# RxPCB_V1-2.net
KiCad netlist of a schematic drawn in EAGLE
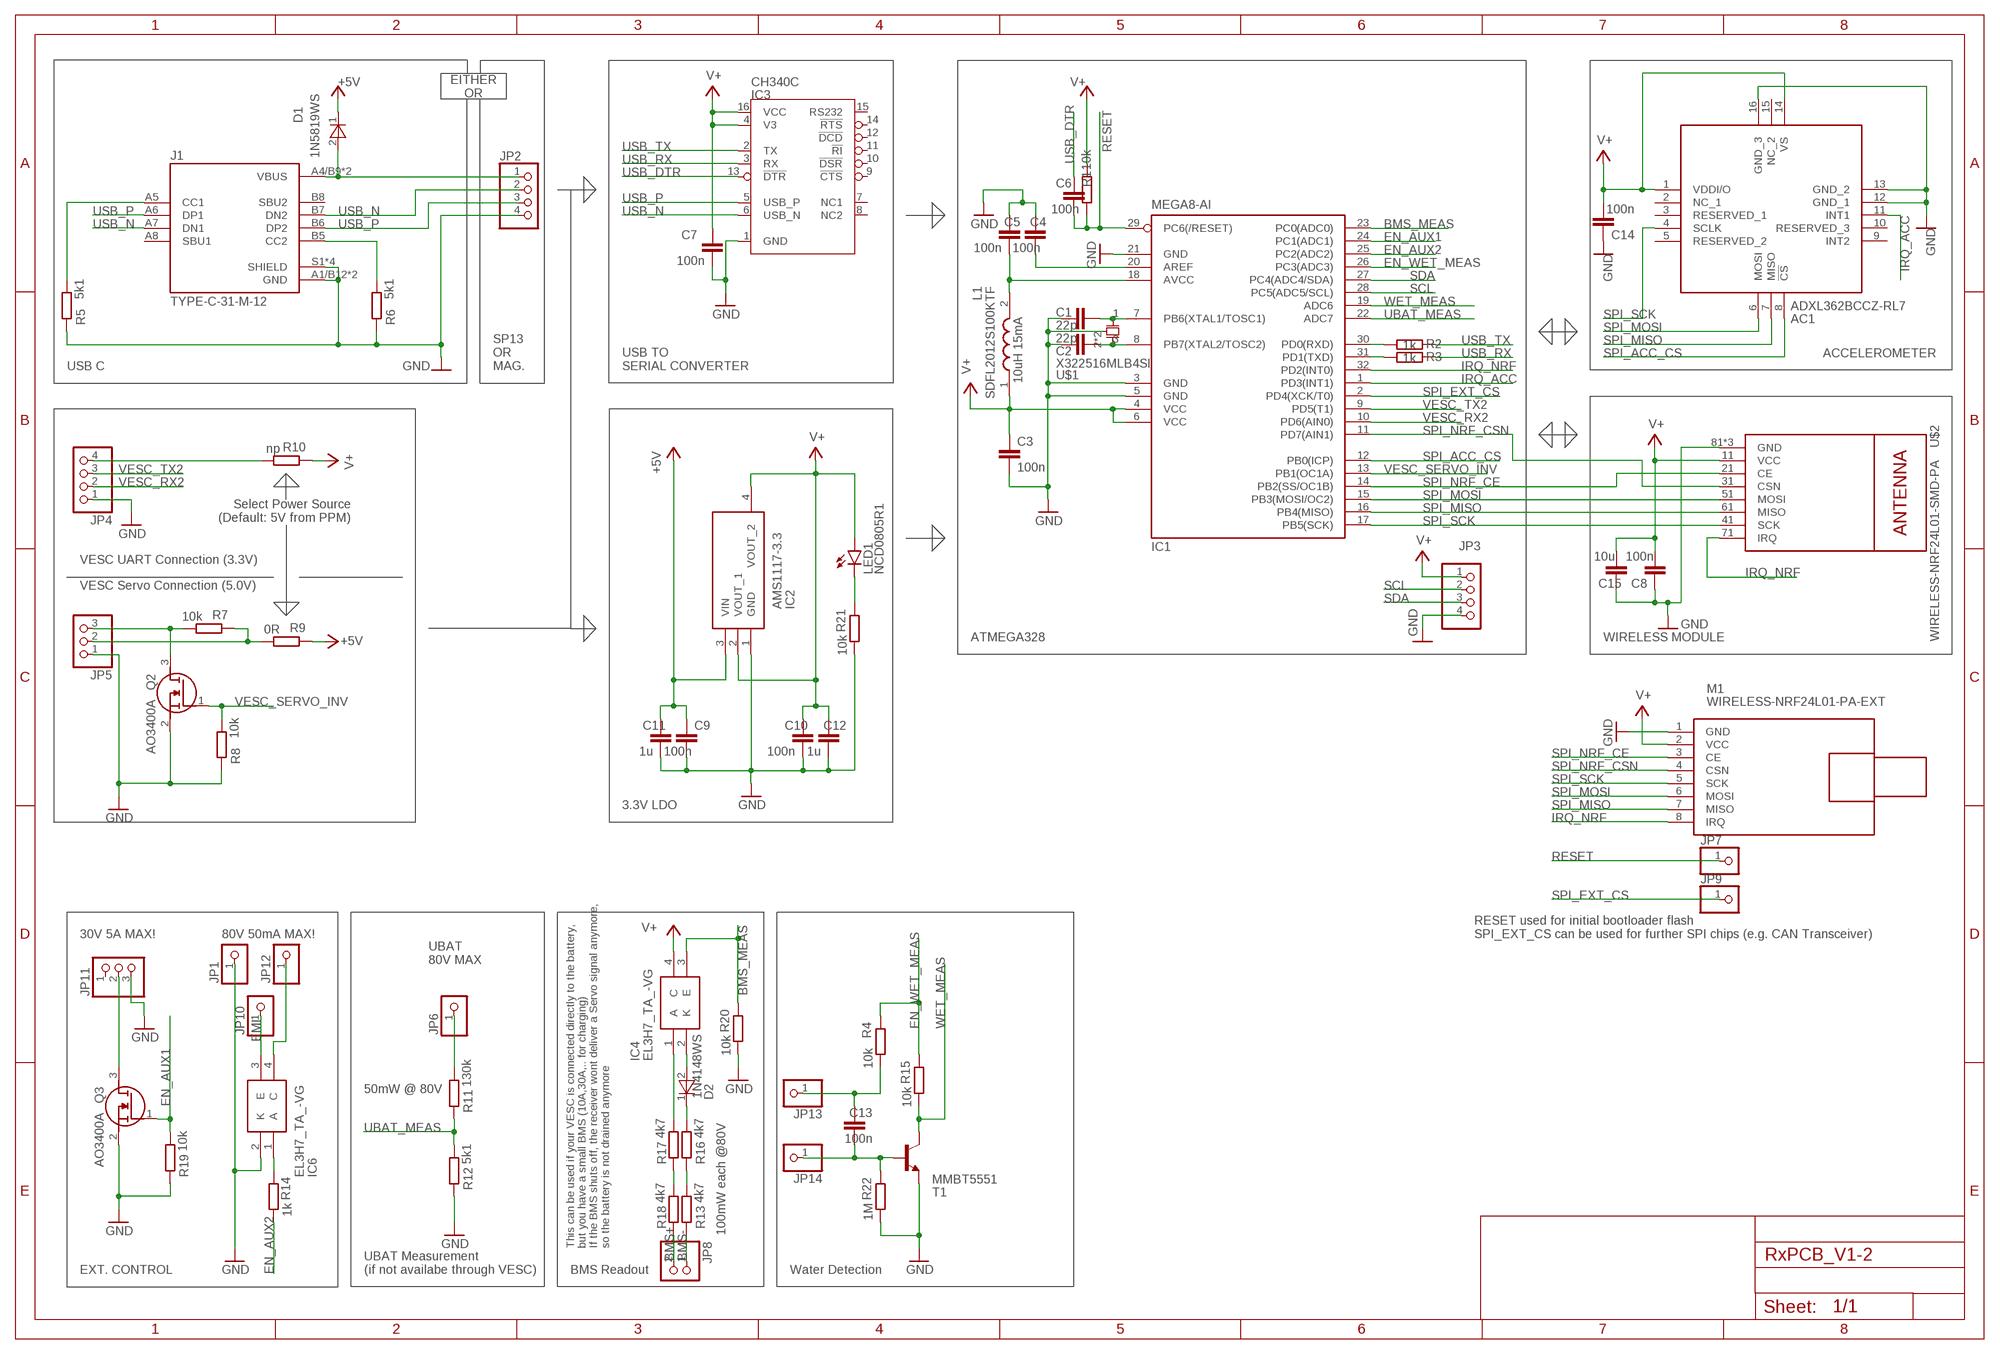
[diagram p0: schematic, sheet 1]

(export (version "E")
  (design (tool "Eeschema 10.0.6"))
  (components
    (comp (ref "AC1")
      (value "ADXL362BCCZ-RL7")
      (footprint "eagle-import:CC-16-4")
      (fields (field (name "MOUSER_PART_NUMBER") "584-ADXL362BCCZ-R7"))
      (libsource (lib "eagle-import") (part "ADXL362BCCZ-RL7"))
    )
    (comp (ref "C1")
      (value "22p")
      (footprint "eagle-import:C0603")
      (libsource (lib "eagle-import") (part "C-EUC0603"))
    )
    (comp (ref "C2")
      (value "22p")
      (footprint "eagle-import:C0603")
      (libsource (lib "eagle-import") (part "C-EUC0603"))
    )
    (comp (ref "C3")
      (value "100n")
      (footprint "eagle-import:C0603")
      (libsource (lib "eagle-import") (part "C-EUC0603"))
    )
    (comp (ref "C4")
      (value "100n")
      (footprint "eagle-import:C0603")
      (libsource (lib "eagle-import") (part "C-EUC0603"))
    )
    (comp (ref "C5")
      (value "100n")
      (footprint "eagle-import:C0603")
      (libsource (lib "eagle-import") (part "C-EUC0603"))
    )
    (comp (ref "C6")
      (value "100n")
      (footprint "eagle-import:C0603")
      (libsource (lib "eagle-import") (part "C-EUC0603"))
    )
    (comp (ref "C7")
      (value "100n")
      (footprint "eagle-import:C0603")
      (libsource (lib "eagle-import") (part "C-EUC0603"))
    )
    (comp (ref "C8")
      (value "100n")
      (footprint "eagle-import:C0603")
      (libsource (lib "eagle-import") (part "C-EUC0603"))
    )
    (comp (ref "C9")
      (value "100n")
      (footprint "eagle-import:C0603")
      (libsource (lib "eagle-import") (part "C-EUC0603"))
    )
    (comp (ref "C10")
      (value "100n")
      (footprint "eagle-import:C0603")
      (libsource (lib "eagle-import") (part "C-EUC0603"))
    )
    (comp (ref "C11")
      (value "1u")
      (footprint "eagle-import:C0603")
      (libsource (lib "eagle-import") (part "C-EUC0603"))
    )
    (comp (ref "C12")
      (value "1u")
      (footprint "eagle-import:C0603")
      (libsource (lib "eagle-import") (part "C-EUC0603"))
    )
    (comp (ref "C13")
      (value "100n")
      (footprint "eagle-import:C0603")
      (libsource (lib "eagle-import") (part "C-EUC0603"))
    )
    (comp (ref "C14")
      (value "100n")
      (footprint "eagle-import:C0603")
      (libsource (lib "eagle-import") (part "C-EUC0603"))
    )
    (comp (ref "C15")
      (value "10u")
      (footprint "eagle-import:C0603")
      (libsource (lib "eagle-import") (part "C-EUC0603"))
    )
    (comp (ref "D1")
      (value "1N5819WS")
      (footprint "eagle-import:SODFL2512X90N")
      (fields
        (field (name "ARROW_PART_NUMBER") "1N4148WS")
        (field (name "MOUSER_PART_NUMBER") "512-1N4148WS")
      )
      (libsource (lib "eagle-import") (part "1N4148WS"))
    )
    (comp (ref "D2")
      (value "1N4148WS")
      (footprint "eagle-import:SODFL2512X90N")
      (fields (field (name "MOUSER_PART_NUMBER") "512-1N4148WS"))
      (libsource (lib "eagle-import") (part "1N4148WS"))
    )
    (comp (ref "IC1")
      (value "MEGA8-AI")
      (footprint "eagle-import:TQFP32-08")
      (fields (field (name "MPN") "ATMEGA8-16AU"))
      (libsource (lib "eagle-import") (part "MEGA8-AI"))
    )
    (comp (ref "IC2")
      (value "AMS1117-3.3")
      (footprint "eagle-import:SOT229P700X180-4N")
      (libsource (lib "eagle-import") (part "AMS1117-3.3"))
    )
    (comp (ref "IC3")
      (value "CH340C")
      (footprint "eagle-import:SOIC16N")
      (libsource (lib "eagle-import") (part "CH340G"))
    )
    (comp (ref "IC4")
      (value "EL3H7_TA_-VG")
      (footprint "eagle-import:SOIC127P700X200-4N")
      (fields
        (field (name "ARROW_PART_NUMBER") "EL3H7(TA)-VG")
        (field (name "MOUSER_PART_NUMBER") "638-EL3H7TAVG")
      )
      (libsource (lib "eagle-import") (part "EL3H7_TA_-VG"))
    )
    (comp (ref "IC6")
      (value "EL3H7_TA_-VG")
      (footprint "eagle-import:SOIC127P700X200-4N")
      (fields
        (field (name "ARROW_PART_NUMBER") "EL3H7(TA)-VG")
        (field (name "MOUSER_PART_NUMBER") "638-EL3H7TAVG")
      )
      (libsource (lib "eagle-import") (part "EL3H7_TA_-VG"))
    )
    (comp (ref "J1")
      (value "TYPE-C-31-M-12")
      (footprint "eagle-import:HRO_TYPE-C-31-M-12")
      (fields (field (name "MF") "HRO Electronics Co., Ltd."))
      (libsource (lib "eagle-import") (part "TYPE-C-31-M-12"))
    )
    (comp (ref "JP1")
      (value "PINHD-1X1")
      (footprint "eagle-import:1X01")
      (libsource (lib "eagle-import") (part "PINHD-1X1"))
    )
    (comp (ref "JP2")
      (value "PINHD-1X4")
      (footprint "eagle-import:1X04")
      (libsource (lib "eagle-import") (part "PINHD-1X4"))
    )
    (comp (ref "JP3")
      (value "PINHD-1X4")
      (footprint "eagle-import:1X04")
      (libsource (lib "eagle-import") (part "PINHD-1X4"))
    )
    (comp (ref "JP4")
      (value "PINHD-1X4")
      (footprint "eagle-import:1X04")
      (libsource (lib "eagle-import") (part "PINHD-1X4"))
    )
    (comp (ref "JP5")
      (value "PINHD-1X3")
      (footprint "eagle-import:1X03")
      (libsource (lib "eagle-import") (part "PINHD-1X3"))
    )
    (comp (ref "JP6")
      (value "PINHD-1X1")
      (footprint "eagle-import:1X01")
      (libsource (lib "eagle-import") (part "PINHD-1X1"))
    )
    (comp (ref "JP7")
      (value "PINHD-1X1")
      (footprint "eagle-import:1X01")
      (libsource (lib "eagle-import") (part "PINHD-1X1"))
    )
    (comp (ref "JP8")
      (value "PINHD-1X2")
      (footprint "eagle-import:1X02")
      (libsource (lib "eagle-import") (part "PINHD-1X2"))
    )
    (comp (ref "JP9")
      (value "PINHD-1X1")
      (footprint "eagle-import:1X01")
      (libsource (lib "eagle-import") (part "PINHD-1X1"))
    )
    (comp (ref "JP10")
      (value "PINHD-1X1")
      (footprint "eagle-import:1X01")
      (libsource (lib "eagle-import") (part "PINHD-1X1"))
    )
    (comp (ref "JP11")
      (value "PINHD-1X3")
      (footprint "eagle-import:1X03")
      (libsource (lib "eagle-import") (part "PINHD-1X3"))
    )
    (comp (ref "JP12")
      (value "PINHD-1X1")
      (footprint "eagle-import:1X01")
      (libsource (lib "eagle-import") (part "PINHD-1X1"))
    )
    (comp (ref "JP13")
      (value "PINHD-1X1")
      (footprint "eagle-import:1X01")
      (libsource (lib "eagle-import") (part "PINHD-1X1"))
    )
    (comp (ref "JP14")
      (value "PINHD-1X1")
      (footprint "eagle-import:1X01")
      (libsource (lib "eagle-import") (part "PINHD-1X1"))
    )
    (comp (ref "L1")
      (value "SDFL2012S100KTF")
      (footprint "eagle-import:INDC2112X105N")
      (fields (field (name "MANUFACTURER_PART_NUMBER") "SDFL2012Q2R7KTF"))
      (libsource (lib "eagle-import") (part "SDFL2012Q2R7KTF"))
    )
    (comp (ref "LED1")
      (value "NCD0805R1")
      (footprint "eagle-import:CHIP-LED0805")
      (libsource (lib "eagle-import") (part "LEDCHIP-LED0805"))
    )
    (comp (ref "M1")
      (value "WIRELESS-NRF24L01-PA-EXT")
      (footprint "eagle-import:WIRELESS-NRF24L01-PA-EXT")
      (libsource (lib "eagle-import") (part "WIRELESS-NRF24L01-PA-EXT"))
    )
    (comp (ref "Q2")
      (value "AO3400A")
      (footprint "eagle-import:SOT95P280X125-3N")
      (libsource (lib "eagle-import") (part "AO3400A"))
    )
    (comp (ref "Q3")
      (value "AO3400A")
      (footprint "eagle-import:SOT95P280X125-3N")
      (libsource (lib "eagle-import") (part "AO3400A"))
    )
    (comp (ref "R1")
      (value "10k")
      (footprint "eagle-import:R0603")
      (libsource (lib "eagle-import") (part "R-EU_R0603"))
    )
    (comp (ref "R2")
      (value "1k")
      (footprint "eagle-import:R0603")
      (libsource (lib "eagle-import") (part "R-EU_R0603"))
    )
    (comp (ref "R3")
      (value "1k")
      (footprint "eagle-import:R0603")
      (libsource (lib "eagle-import") (part "R-EU_R0603"))
    )
    (comp (ref "R4")
      (value "10k")
      (footprint "eagle-import:R0603")
      (libsource (lib "eagle-import") (part "R-EU_R0603"))
    )
    (comp (ref "R5")
      (value "5k1")
      (footprint "eagle-import:R0603")
      (libsource (lib "eagle-import") (part "R-EU_R0603"))
    )
    (comp (ref "R6")
      (value "5k1")
      (footprint "eagle-import:R0603")
      (libsource (lib "eagle-import") (part "R-EU_R0603"))
    )
    (comp (ref "R7")
      (value "10k")
      (footprint "eagle-import:R0603")
      (libsource (lib "eagle-import") (part "R-EU_R0603"))
    )
    (comp (ref "R8")
      (value "10k")
      (footprint "eagle-import:R0603")
      (libsource (lib "eagle-import") (part "R-EU_R0603"))
    )
    (comp (ref "R9")
      (value "0R")
      (footprint "eagle-import:R0603")
      (libsource (lib "eagle-import") (part "R-EU_R0603"))
    )
    (comp (ref "R10")
      (value "np")
      (footprint "eagle-import:R0603")
      (libsource (lib "eagle-import") (part "R-EU_R0603"))
    )
    (comp (ref "R11")
      (value "130k")
      (footprint "eagle-import:R0603")
      (libsource (lib "eagle-import") (part "R-EU_R0603"))
    )
    (comp (ref "R12")
      (value "5k1")
      (footprint "eagle-import:R0603")
      (libsource (lib "eagle-import") (part "R-EU_R0603"))
    )
    (comp (ref "R13")
      (value "4k7")
      (footprint "eagle-import:R0603")
      (libsource (lib "eagle-import") (part "R-EU_R0603"))
    )
    (comp (ref "R14")
      (value "1k")
      (footprint "eagle-import:R0603")
      (libsource (lib "eagle-import") (part "R-EU_R0603"))
    )
    (comp (ref "R15")
      (value "10k")
      (footprint "eagle-import:R0603")
      (libsource (lib "eagle-import") (part "R-EU_R0603"))
    )
    (comp (ref "R16")
      (value "4k7")
      (footprint "eagle-import:R0603")
      (libsource (lib "eagle-import") (part "R-EU_R0603"))
    )
    (comp (ref "R17")
      (value "4k7")
      (footprint "eagle-import:R0603")
      (libsource (lib "eagle-import") (part "R-EU_R0603"))
    )
    (comp (ref "R18")
      (value "4k7")
      (footprint "eagle-import:R0603")
      (libsource (lib "eagle-import") (part "R-EU_R0603"))
    )
    (comp (ref "R19")
      (value "10k")
      (footprint "eagle-import:R0603")
      (libsource (lib "eagle-import") (part "R-EU_R0603"))
    )
    (comp (ref "R20")
      (value "10k")
      (footprint "eagle-import:R0603")
      (libsource (lib "eagle-import") (part "R-EU_R0603"))
    )
    (comp (ref "R21")
      (value "10k")
      (footprint "eagle-import:R0603")
      (libsource (lib "eagle-import") (part "R-EU_R0603"))
    )
    (comp (ref "R22")
      (value "1M")
      (footprint "eagle-import:R0603")
      (libsource (lib "eagle-import") (part "R-EU_R0603"))
    )
    (comp (ref "T1")
      (value "MMBT5551")
      (footprint "eagle-import:SOT23-BEC")
      (libsource (lib "eagle-import") (part "-NPN-SOT23-BECBC847B"))
    )
    (comp (ref "U$1")
      (value "X322516MLB4SI")
      (footprint "eagle-import:X322516MLB4SI")
      (libsource (lib "eagle-import") (part "X322516_BETTER"))
    )
    (comp (ref "U$2")
      (value "WIRELESS-NRF24L01-SMD-PA")
      (footprint "eagle-import:WIRELESS-NRF24L01_SMD_PA")
      (libsource (lib "eagle-import") (part "WIRELESS-NRF24L01-SMD-PA"))
    )
  )
  (nets
    (net (code "1") (name "+5V") (class "Default")
      (node (ref "C11") (pin "1") (pinfunction "1_1") (pintype "passive"))
      (node (ref "C9") (pin "1") (pinfunction "1_1") (pintype "passive"))
      (node (ref "D1") (pin "1") (pinfunction "K_1") (pintype "bidirectional"))
      (node (ref "IC2") (pin "3") (pinfunction "VIN_3") (pintype "bidirectional"))
      (node (ref "R9") (pin "1") (pinfunction "1_1") (pintype "passive"))
    )
    (net (code "2") (name "/BMS+") (class "Default")
      (node (ref "JP8") (pin "2") (pinfunction "2_2") (pintype "passive"))
      (node (ref "R18") (pin "1") (pinfunction "1_1") (pintype "passive"))
    )
    (net (code "3") (name "/BMS-") (class "Default")
      (node (ref "JP8") (pin "1") (pinfunction "1_1") (pintype "passive"))
      (node (ref "R13") (pin "1") (pinfunction "1_1") (pintype "passive"))
    )
    (net (code "4") (name "/BMS_MEAS") (class "Default")
      (node (ref "IC1") (pin "23") (pinfunction "PC0(ADC0)_23") (pintype "bidirectional"))
      (node (ref "IC4") (pin "3") (pinfunction "E_3") (pintype "bidirectional"))
      (node (ref "R20") (pin "1") (pinfunction "1_1") (pintype "passive"))
    )
    (net (code "5") (name "/EMI") (class "Default")
      (node (ref "IC6") (pin "3") (pinfunction "E_3") (pintype "bidirectional"))
      (node (ref "JP10") (pin "1") (pinfunction "1_1") (pintype "passive"))
    )
    (net (code "6") (name "/EN_AUX1") (class "Default")
      (node (ref "IC1") (pin "24") (pinfunction "PC1(ADC1)_24") (pintype "bidirectional"))
      (node (ref "Q3") (pin "1") (pinfunction "G_1") (pintype "bidirectional"))
      (node (ref "R19") (pin "2") (pinfunction "2_2") (pintype "passive"))
    )
    (net (code "7") (name "/EN_AUX2") (class "Default")
      (node (ref "IC1") (pin "25") (pinfunction "PC2(ADC2)_25") (pintype "bidirectional"))
      (node (ref "R14") (pin "2") (pinfunction "2_2") (pintype "passive"))
    )
    (net (code "8") (name "/EN_WET_MEAS") (class "Default")
      (node (ref "IC1") (pin "26") (pinfunction "PC3(ADC3)_26") (pintype "bidirectional"))
      (node (ref "R15") (pin "1") (pinfunction "1_1") (pintype "passive"))
      (node (ref "R4") (pin "1") (pinfunction "1_1") (pintype "passive"))
    )
    (net (code "9") (name "/IRQ_ACC") (class "Default")
      (node (ref "AC1") (pin "11") (pinfunction "INT1_11") (pintype "input"))
      (node (ref "IC1") (pin "1") (pinfunction "PD3(INT1)_1") (pintype "bidirectional"))
    )
    (net (code "10") (name "/IRQ_NRF") (class "Default")
      (node (ref "IC1") (pin "32") (pinfunction "PD2(INT0)_32") (pintype "bidirectional"))
      (node (ref "M1") (pin "8") (pinfunction "IRQ_8") (pintype "bidirectional"))
      (node (ref "U$2") (pin "71") (pinfunction "IRQ_71") (pintype "bidirectional"))
    )
    (net (code "11") (name "/RESET") (class "Default")
      (node (ref "C6") (pin "2") (pinfunction "2_2") (pintype "passive"))
      (node (ref "IC1") (pin "29") (pinfunction "PC6(/RESET)_29") (pintype "bidirectional"))
      (node (ref "JP7") (pin "1") (pinfunction "1_1") (pintype "passive"))
      (node (ref "R1") (pin "1") (pinfunction "1_1") (pintype "passive"))
    )
    (net (code "12") (name "/SCL") (class "Default")
      (node (ref "IC1") (pin "28") (pinfunction "PC5(ADC5/SCL)_28") (pintype "bidirectional"))
      (node (ref "JP3") (pin "2") (pinfunction "2_2") (pintype "passive"))
    )
    (net (code "13") (name "/SDA") (class "Default")
      (node (ref "IC1") (pin "27") (pinfunction "PC4(ADC4/SDA)_27") (pintype "bidirectional"))
      (node (ref "JP3") (pin "3") (pinfunction "3_3") (pintype "passive"))
    )
    (net (code "14") (name "/SPI_ACC_CS") (class "Default")
      (node (ref "AC1") (pin "8") (pinfunction "~{CS}_8") (pintype "input"))
      (node (ref "IC1") (pin "12") (pinfunction "PB0(ICP)_12") (pintype "bidirectional"))
    )
    (net (code "15") (name "/SPI_EXT_CS") (class "Default")
      (node (ref "IC1") (pin "2") (pinfunction "PD4(XCK/T0)_2") (pintype "bidirectional"))
      (node (ref "JP9") (pin "1") (pinfunction "1_1") (pintype "passive"))
    )
    (net (code "16") (name "/SPI_MISO") (class "Default")
      (node (ref "AC1") (pin "7") (pinfunction "MISO_7") (pintype "bidirectional"))
      (node (ref "IC1") (pin "16") (pinfunction "PB4(MISO)_16") (pintype "bidirectional"))
      (node (ref "M1") (pin "7") (pinfunction "MISO_7") (pintype "bidirectional"))
      (node (ref "U$2") (pin "61") (pinfunction "MISO_61") (pintype "bidirectional"))
    )
    (net (code "17") (name "/SPI_MOSI") (class "Default")
      (node (ref "AC1") (pin "6") (pinfunction "MOSI_6") (pintype "bidirectional"))
      (node (ref "IC1") (pin "15") (pinfunction "PB3(MOSI/OC2)_15") (pintype "bidirectional"))
      (node (ref "M1") (pin "6") (pinfunction "MOSI_6") (pintype "bidirectional"))
      (node (ref "U$2") (pin "51") (pinfunction "MOSI_51") (pintype "bidirectional"))
    )
    (net (code "18") (name "/SPI_NRF_CE") (class "Default")
      (node (ref "IC1") (pin "14") (pinfunction "PB2(SS/OC1B)_14") (pintype "bidirectional"))
      (node (ref "M1") (pin "3") (pinfunction "CE_3") (pintype "bidirectional"))
      (node (ref "U$2") (pin "21") (pinfunction "CE_21") (pintype "bidirectional"))
    )
    (net (code "19") (name "/SPI_NRF_CSN") (class "Default")
      (node (ref "IC1") (pin "11") (pinfunction "PD7(AIN1)_11") (pintype "bidirectional"))
      (node (ref "M1") (pin "4") (pinfunction "CSN_4") (pintype "bidirectional"))
      (node (ref "U$2") (pin "31") (pinfunction "CSN_31") (pintype "bidirectional"))
    )
    (net (code "20") (name "/SPI_SCK") (class "Default")
      (node (ref "AC1") (pin "4") (pinfunction "SCLK_4") (pintype "input"))
      (node (ref "IC1") (pin "17") (pinfunction "PB5(SCK)_17") (pintype "bidirectional"))
      (node (ref "M1") (pin "5") (pinfunction "SCK_5") (pintype "bidirectional"))
      (node (ref "U$2") (pin "41") (pinfunction "SCK_41") (pintype "bidirectional"))
    )
    (net (code "21") (name "/UBAT_MEAS") (class "Default")
      (node (ref "IC1") (pin "22") (pinfunction "ADC7_22") (pintype "bidirectional"))
      (node (ref "R11") (pin "1") (pinfunction "1_1") (pintype "passive"))
      (node (ref "R12") (pin "2") (pinfunction "2_2") (pintype "passive"))
    )
    (net (code "22") (name "/USB_DTR") (class "Default")
      (node (ref "C6") (pin "1") (pinfunction "1_1") (pintype "passive"))
      (node (ref "IC3") (pin "13") (pinfunction "~{DTR}_13") (pintype "output"))
    )
    (net (code "23") (name "/USB_N") (class "Default")
      (node (ref "IC3") (pin "6") (pinfunction "USB_N_6") (pintype "bidirectional"))
      (node (ref "J1") (pin "A7") (pinfunction "DN1_A7") (pintype "bidirectional"))
      (node (ref "J1") (pin "B7") (pinfunction "DN2_B7") (pintype "bidirectional"))
      (node (ref "JP2") (pin "2") (pinfunction "2_2") (pintype "passive"))
    )
    (net (code "24") (name "/USB_P") (class "Default")
      (node (ref "IC3") (pin "5") (pinfunction "USB_P_5") (pintype "bidirectional"))
      (node (ref "J1") (pin "A6") (pinfunction "DP1_A6") (pintype "bidirectional"))
      (node (ref "J1") (pin "B6") (pinfunction "DP2_B6") (pintype "bidirectional"))
      (node (ref "JP2") (pin "3") (pinfunction "3_3") (pintype "passive"))
    )
    (net (code "25") (name "/USB_RX") (class "Default")
      (node (ref "IC3") (pin "3") (pinfunction "RX_3") (pintype "input"))
      (node (ref "R3") (pin "1") (pinfunction "1_1") (pintype "passive"))
    )
    (net (code "26") (name "/USB_TX") (class "Default")
      (node (ref "IC3") (pin "2") (pinfunction "TX_2") (pintype "output"))
      (node (ref "R2") (pin "1") (pinfunction "1_1") (pintype "passive"))
    )
    (net (code "27") (name "/VESC_RX2") (class "Default")
      (node (ref "IC1") (pin "10") (pinfunction "PD6(AIN0)_10") (pintype "bidirectional"))
      (node (ref "JP4") (pin "2") (pinfunction "2_2") (pintype "passive"))
    )
    (net (code "28") (name "/VESC_SERVO_INV") (class "Default")
      (node (ref "IC1") (pin "13") (pinfunction "PB1(OC1A)_13") (pintype "bidirectional"))
      (node (ref "Q2") (pin "1") (pinfunction "G_1") (pintype "bidirectional"))
      (node (ref "R8") (pin "2") (pinfunction "2_2") (pintype "passive"))
    )
    (net (code "29") (name "/VESC_TX2") (class "Default")
      (node (ref "IC1") (pin "9") (pinfunction "PD5(T1)_9") (pintype "bidirectional"))
      (node (ref "JP4") (pin "3") (pinfunction "3_3") (pintype "passive"))
    )
    (net (code "30") (name "/WET_MEAS") (class "Default")
      (node (ref "IC1") (pin "19") (pinfunction "ADC6_19") (pintype "bidirectional"))
      (node (ref "R15") (pin "2") (pinfunction "2_2") (pintype "passive"))
      (node (ref "T1") (pin "C") (pinfunction "C_C") (pintype "passive"))
    )
    (net (code "31") (name "GND") (class "Default")
      (node (ref "AC1") (pin "12") (pinfunction "GND_1_12") (pintype "power_in"))
      (node (ref "AC1") (pin "13") (pinfunction "GND_2_13") (pintype "power_in"))
      (node (ref "AC1") (pin "16") (pinfunction "GND_3_16") (pintype "power_in"))
      (node (ref "C1") (pin "2") (pinfunction "2_2") (pintype "passive"))
      (node (ref "C10") (pin "2") (pinfunction "2_2") (pintype "passive"))
      (node (ref "C11") (pin "2") (pinfunction "2_2") (pintype "passive"))
      (node (ref "C12") (pin "2") (pinfunction "2_2") (pintype "passive"))
      (node (ref "C14") (pin "1") (pinfunction "1_1") (pintype "passive"))
      (node (ref "C15") (pin "2") (pinfunction "2_2") (pintype "passive"))
      (node (ref "C2") (pin "2") (pinfunction "2_2") (pintype "passive"))
      (node (ref "C3") (pin "2") (pinfunction "2_2") (pintype "passive"))
      (node (ref "C4") (pin "1") (pinfunction "1_1") (pintype "passive"))
      (node (ref "C5") (pin "1") (pinfunction "1_1") (pintype "passive"))
      (node (ref "C7") (pin "2") (pinfunction "2_2") (pintype "passive"))
      (node (ref "C8") (pin "1") (pinfunction "1_1") (pintype "passive"))
      (node (ref "C9") (pin "2") (pinfunction "2_2") (pintype "passive"))
      (node (ref "IC1") (pin "21") (pinfunction "GND_21") (pintype "power_in"))
      (node (ref "IC1") (pin "3") (pinfunction "GND_3") (pintype "power_in"))
      (node (ref "IC1") (pin "5") (pinfunction "GND_5") (pintype "power_in"))
      (node (ref "IC2") (pin "1") (pinfunction "GND_1") (pintype "bidirectional"))
      (node (ref "IC3") (pin "1") (pinfunction "GND_1") (pintype "input"))
      (node (ref "IC6") (pin "2") (pinfunction "K_2") (pintype "bidirectional"))
      (node (ref "J1") (pin "A1/B12") (pinfunction "GND_A1/B12") (pintype "power_in"))
      (node (ref "J1") (pin "B1/A12") (pinfunction "GND_B1/A12") (pintype "power_in"))
      (node (ref "J1") (pin "S1") (pinfunction "SHIELD_S1") (pintype "passive"))
      (node (ref "J1") (pin "S2") (pinfunction "SHIELD_S2") (pintype "passive"))
      (node (ref "J1") (pin "S3") (pinfunction "SHIELD_S3") (pintype "passive"))
      (node (ref "J1") (pin "S4") (pinfunction "SHIELD_S4") (pintype "passive"))
      (node (ref "JP1") (pin "1") (pinfunction "1_1") (pintype "passive"))
      (node (ref "JP11") (pin "3") (pinfunction "3_3") (pintype "passive"))
      (node (ref "JP2") (pin "4") (pinfunction "4_4") (pintype "passive"))
      (node (ref "JP3") (pin "4") (pinfunction "4_4") (pintype "passive"))
      (node (ref "JP4") (pin "1") (pinfunction "1_1") (pintype "passive"))
      (node (ref "JP5") (pin "1") (pinfunction "1_1") (pintype "passive"))
      (node (ref "M1") (pin "1") (pinfunction "GND_1") (pintype "power_in"))
      (node (ref "Q2") (pin "2") (pinfunction "S_2") (pintype "bidirectional"))
      (node (ref "Q3") (pin "2") (pinfunction "S_2") (pintype "bidirectional"))
      (node (ref "R12") (pin "1") (pinfunction "1_1") (pintype "passive"))
      (node (ref "R19") (pin "1") (pinfunction "1_1") (pintype "passive"))
      (node (ref "R20") (pin "2") (pinfunction "2_2") (pintype "passive"))
      (node (ref "R21") (pin "2") (pinfunction "2_2") (pintype "passive"))
      (node (ref "R22") (pin "2") (pinfunction "2_2") (pintype "passive"))
      (node (ref "R5") (pin "1") (pinfunction "1_1") (pintype "passive"))
      (node (ref "R6") (pin "1") (pinfunction "1_1") (pintype "passive"))
      (node (ref "R8") (pin "1") (pinfunction "1_1") (pintype "passive"))
      (node (ref "T1") (pin "E") (pinfunction "E_E") (pintype "passive"))
      (node (ref "U$1") (pin "2") (pinfunction "G_2") (pintype "bidirectional"))
      (node (ref "U$1") (pin "4") (pinfunction "G_4") (pintype "bidirectional"))
      (node (ref "U$2") (pin "81") (pinfunction "GND_81") (pintype "power_in"))
      (node (ref "U$2") (pin "P1") (pinfunction "GND_P1") (pintype "power_in"))
      (node (ref "U$2") (pin "P2") (pinfunction "GND_P2") (pintype "power_in"))
    )
    (net (code "32") (name "Net-(C13-Pad1)") (class "Default")
      (node (ref "C13") (pin "1") (pinfunction "1_1") (pintype "passive"))
      (node (ref "JP13") (pin "1") (pinfunction "1_1") (pintype "passive"))
      (node (ref "R4") (pin "2") (pinfunction "2_2") (pintype "passive"))
    )
    (net (code "33") (name "Net-(C13-Pad2)") (class "Default")
      (node (ref "C13") (pin "2") (pinfunction "2_2") (pintype "passive"))
      (node (ref "JP14") (pin "1") (pinfunction "1_1") (pintype "passive"))
      (node (ref "R22") (pin "1") (pinfunction "1_1") (pintype "passive"))
      (node (ref "T1") (pin "B") (pinfunction "B_B") (pintype "passive"))
    )
    (net (code "34") (name "Net-(D1-A)") (class "Default")
      (node (ref "D1") (pin "2") (pinfunction "A_2") (pintype "bidirectional"))
      (node (ref "J1") (pin "A4/B9") (pinfunction "VBUS_A4/B9") (pintype "power_in"))
      (node (ref "J1") (pin "B4/A9") (pinfunction "VBUS_B4/A9") (pintype "power_in"))
      (node (ref "JP2") (pin "1") (pinfunction "1_1") (pintype "passive"))
    )
    (net (code "35") (name "Net-(D2-A)") (class "Default")
      (node (ref "D2") (pin "2") (pinfunction "A_2") (pintype "bidirectional"))
      (node (ref "IC4") (pin "2") (pinfunction "K_2") (pintype "bidirectional"))
    )
    (net (code "36") (name "Net-(D2-K)") (class "Default")
      (node (ref "D2") (pin "1") (pinfunction "K_1") (pintype "bidirectional"))
      (node (ref "R16") (pin "2") (pinfunction "2_2") (pintype "passive"))
    )
    (net (code "37") (name "Net-(IC1-AREF)") (class "Default")
      (node (ref "C4") (pin "2") (pinfunction "2_2") (pintype "passive"))
      (node (ref "IC1") (pin "20") (pinfunction "AREF_20") (pintype "passive"))
    )
    (net (code "38") (name "Net-(IC1-AVCC)") (class "Default")
      (node (ref "C5") (pin "2") (pinfunction "2_2") (pintype "passive"))
      (node (ref "IC1") (pin "18") (pinfunction "AVCC_18") (pintype "power_in"))
      (node (ref "L1") (pin "2") (pinfunction "2_2") (pintype "bidirectional"))
    )
    (net (code "39") (name "Net-(IC1-PB6(XTAL1{slash}TOSC1))") (class "Default")
      (node (ref "C1") (pin "1") (pinfunction "1_1") (pintype "passive"))
      (node (ref "IC1") (pin "7") (pinfunction "PB6(XTAL1/TOSC1)_7") (pintype "bidirectional"))
      (node (ref "U$1") (pin "1") (pinfunction "X1_1") (pintype "bidirectional"))
    )
    (net (code "40") (name "Net-(IC1-PB7(XTAL2{slash}TOSC2))") (class "Default")
      (node (ref "C2") (pin "1") (pinfunction "1_1") (pintype "passive"))
      (node (ref "IC1") (pin "8") (pinfunction "PB7(XTAL2/TOSC2)_8") (pintype "bidirectional"))
      (node (ref "U$1") (pin "3") (pinfunction "X2_3") (pintype "bidirectional"))
    )
    (net (code "41") (name "Net-(IC1-PD0(RXD))") (class "Default")
      (node (ref "IC1") (pin "30") (pinfunction "PD0(RXD)_30") (pintype "bidirectional"))
      (node (ref "R2") (pin "2") (pinfunction "2_2") (pintype "passive"))
    )
    (net (code "42") (name "Net-(IC1-PD1(TXD))") (class "Default")
      (node (ref "IC1") (pin "31") (pinfunction "PD1(TXD)_31") (pintype "bidirectional"))
      (node (ref "R3") (pin "2") (pinfunction "2_2") (pintype "passive"))
    )
    (net (code "43") (name "Net-(IC4-A)") (class "Default")
      (node (ref "IC4") (pin "1") (pinfunction "A_1") (pintype "bidirectional"))
      (node (ref "R17") (pin "2") (pinfunction "2_2") (pintype "passive"))
    )
    (net (code "44") (name "Net-(IC6-A)") (class "Default")
      (node (ref "IC6") (pin "1") (pinfunction "A_1") (pintype "bidirectional"))
      (node (ref "R14") (pin "1") (pinfunction "1_1") (pintype "passive"))
    )
    (net (code "45") (name "Net-(IC6-C)") (class "Default")
      (node (ref "IC6") (pin "4") (pinfunction "C_4") (pintype "bidirectional"))
      (node (ref "JP12") (pin "1") (pinfunction "1_1") (pintype "passive"))
    )
    (net (code "46") (name "Net-(J1-CC1)") (class "Default")
      (node (ref "J1") (pin "A5") (pinfunction "CC1_A5") (pintype "bidirectional"))
      (node (ref "R5") (pin "2") (pinfunction "2_2") (pintype "passive"))
    )
    (net (code "47") (name "Net-(J1-CC2)") (class "Default")
      (node (ref "J1") (pin "B5") (pinfunction "CC2_B5") (pintype "bidirectional"))
      (node (ref "R6") (pin "2") (pinfunction "2_2") (pintype "passive"))
    )
    (net (code "48") (name "Net-(JP4-Pad4)") (class "Default")
      (node (ref "JP4") (pin "4") (pinfunction "4_4") (pintype "passive"))
      (node (ref "R10") (pin "2") (pinfunction "2_2") (pintype "passive"))
    )
    (net (code "49") (name "Net-(JP5-Pad2)") (class "Default")
      (node (ref "JP5") (pin "2") (pinfunction "2_2") (pintype "passive"))
      (node (ref "R7") (pin "1") (pinfunction "1_1") (pintype "passive"))
      (node (ref "R9") (pin "2") (pinfunction "2_2") (pintype "passive"))
    )
    (net (code "50") (name "Net-(JP6-Pad1)") (class "Default")
      (node (ref "JP6") (pin "1") (pinfunction "1_1") (pintype "passive"))
      (node (ref "R11") (pin "2") (pinfunction "2_2") (pintype "passive"))
    )
    (net (code "51") (name "Net-(LED1-PadC)") (class "Default")
      (node (ref "LED1") (pin "C") (pinfunction "C_C") (pintype "passive"))
      (node (ref "R21") (pin "1") (pinfunction "1_1") (pintype "passive"))
    )
    (net (code "52") (name "Net-(Q2-D)") (class "Default")
      (node (ref "JP5") (pin "3") (pinfunction "3_3") (pintype "passive"))
      (node (ref "Q2") (pin "3") (pinfunction "D_3") (pintype "bidirectional"))
      (node (ref "R7") (pin "2") (pinfunction "2_2") (pintype "passive"))
    )
    (net (code "53") (name "Net-(Q3-D)") (class "Default")
      (node (ref "JP11") (pin "2") (pinfunction "2_2") (pintype "passive"))
      (node (ref "Q3") (pin "3") (pinfunction "D_3") (pintype "bidirectional"))
    )
    (net (code "54") (name "Net-(R13-Pad2)") (class "Default")
      (node (ref "R13") (pin "2") (pinfunction "2_2") (pintype "passive"))
      (node (ref "R16") (pin "1") (pinfunction "1_1") (pintype "passive"))
    )
    (net (code "55") (name "Net-(R17-Pad1)") (class "Default")
      (node (ref "R17") (pin "1") (pinfunction "1_1") (pintype "passive"))
      (node (ref "R18") (pin "2") (pinfunction "2_2") (pintype "passive"))
    )
    (net (code "56") (name "V+") (class "Default")
      (node (ref "AC1") (pin "1") (pinfunction "VDDI/O_1") (pintype "power_in"))
      (node (ref "AC1") (pin "14") (pinfunction "VS_14") (pintype "bidirectional"))
      (node (ref "C10") (pin "1") (pinfunction "1_1") (pintype "passive"))
      (node (ref "C12") (pin "1") (pinfunction "1_1") (pintype "passive"))
      (node (ref "C14") (pin "2") (pinfunction "2_2") (pintype "passive"))
      (node (ref "C15") (pin "1") (pinfunction "1_1") (pintype "passive"))
      (node (ref "C3") (pin "1") (pinfunction "1_1") (pintype "passive"))
      (node (ref "C7") (pin "1") (pinfunction "1_1") (pintype "passive"))
      (node (ref "C8") (pin "2") (pinfunction "2_2") (pintype "passive"))
      (node (ref "IC1") (pin "4") (pinfunction "VCC_4") (pintype "power_in"))
      (node (ref "IC1") (pin "6") (pinfunction "VCC_6") (pintype "power_in"))
      (node (ref "IC2") (pin "2") (pinfunction "VOUT_1_2") (pintype "bidirectional"))
      (node (ref "IC2") (pin "4") (pinfunction "VOUT_2_4") (pintype "bidirectional"))
      (node (ref "IC3") (pin "16") (pinfunction "VCC_16") (pintype "input"))
      (node (ref "IC3") (pin "4") (pinfunction "V3_4") (pintype "output"))
      (node (ref "IC4") (pin "4") (pinfunction "C_4") (pintype "bidirectional"))
      (node (ref "JP3") (pin "1") (pinfunction "1_1") (pintype "passive"))
      (node (ref "L1") (pin "1") (pinfunction "1_1") (pintype "bidirectional"))
      (node (ref "LED1") (pin "A") (pinfunction "A_A") (pintype "passive"))
      (node (ref "M1") (pin "2") (pinfunction "VCC_2") (pintype "power_in"))
      (node (ref "R1") (pin "2") (pinfunction "2_2") (pintype "passive"))
      (node (ref "R10") (pin "1") (pinfunction "1_1") (pintype "passive"))
      (node (ref "U$2") (pin "11") (pinfunction "VCC_11") (pintype "power_in"))
    )
    (net (code "57") (name "unconnected-(AC1-INT2-Pad9)") (class "Default")
      (node (ref "AC1") (pin "9") (pinfunction "INT2_9") (pintype "input"))
    )
    (net (code "58") (name "unconnected-(AC1-NC_1-Pad2)") (class "Default")
      (node (ref "AC1") (pin "2") (pinfunction "NC_1_2") (pintype "bidirectional"))
    )
    (net (code "59") (name "unconnected-(AC1-NC_2-Pad15)") (class "Default")
      (node (ref "AC1") (pin "15") (pinfunction "NC_2_15") (pintype "bidirectional"))
    )
    (net (code "60") (name "unconnected-(AC1-RESERVED_1-Pad3)") (class "Default")
      (node (ref "AC1") (pin "3") (pinfunction "RESERVED_1_3") (pintype "bidirectional"))
    )
    (net (code "61") (name "unconnected-(AC1-RESERVED_2-Pad5)") (class "Default")
      (node (ref "AC1") (pin "5") (pinfunction "RESERVED_2_5") (pintype "bidirectional"))
    )
    (net (code "62") (name "unconnected-(AC1-RESERVED_3-Pad10)") (class "Default")
      (node (ref "AC1") (pin "10") (pinfunction "RESERVED_3_10") (pintype "bidirectional"))
    )
    (net (code "63") (name "unconnected-(IC3-NC1-Pad7)") (class "Default")
      (node (ref "IC3") (pin "7") (pinfunction "NC1_7") (pintype "no_connect"))
    )
    (net (code "64") (name "unconnected-(IC3-NC2-Pad8)") (class "Default")
      (node (ref "IC3") (pin "8") (pinfunction "NC2_8") (pintype "no_connect"))
    )
    (net (code "65") (name "unconnected-(IC3-RS232-Pad15)") (class "Default")
      (node (ref "IC3") (pin "15") (pinfunction "RS232_15") (pintype "input"))
    )
    (net (code "66") (name "unconnected-(IC3-~{CTS}-Pad9)") (class "Default")
      (node (ref "IC3") (pin "9") (pinfunction "~{CTS}_9") (pintype "input"))
    )
    (net (code "67") (name "unconnected-(IC3-~{DCD}-Pad12)") (class "Default")
      (node (ref "IC3") (pin "12") (pinfunction "~{DCD}_12") (pintype "input"))
    )
    (net (code "68") (name "unconnected-(IC3-~{DSR}-Pad10)") (class "Default")
      (node (ref "IC3") (pin "10") (pinfunction "~{DSR}_10") (pintype "input"))
    )
    (net (code "69") (name "unconnected-(IC3-~{RI}-Pad11)") (class "Default")
      (node (ref "IC3") (pin "11") (pinfunction "~{RI}_11") (pintype "input"))
    )
    (net (code "70") (name "unconnected-(IC3-~{RTS}-Pad14)") (class "Default")
      (node (ref "IC3") (pin "14") (pinfunction "~{RTS}_14") (pintype "output"))
    )
    (net (code "71") (name "unconnected-(J1-SBU1-PadA8)") (class "Default")
      (node (ref "J1") (pin "A8") (pinfunction "SBU1_A8") (pintype "bidirectional"))
    )
    (net (code "72") (name "unconnected-(J1-SBU2-PadB8)") (class "Default")
      (node (ref "J1") (pin "B8") (pinfunction "SBU2_B8") (pintype "bidirectional"))
    )
    (net (code "73") (name "unconnected-(JP11-Pad1)") (class "Default")
      (node (ref "JP11") (pin "1") (pinfunction "1_1") (pintype "passive"))
    )
  )
)
